# 10_ToMeasOutUI.net
KiCad netlist of a schematic drawn in Altium Designer
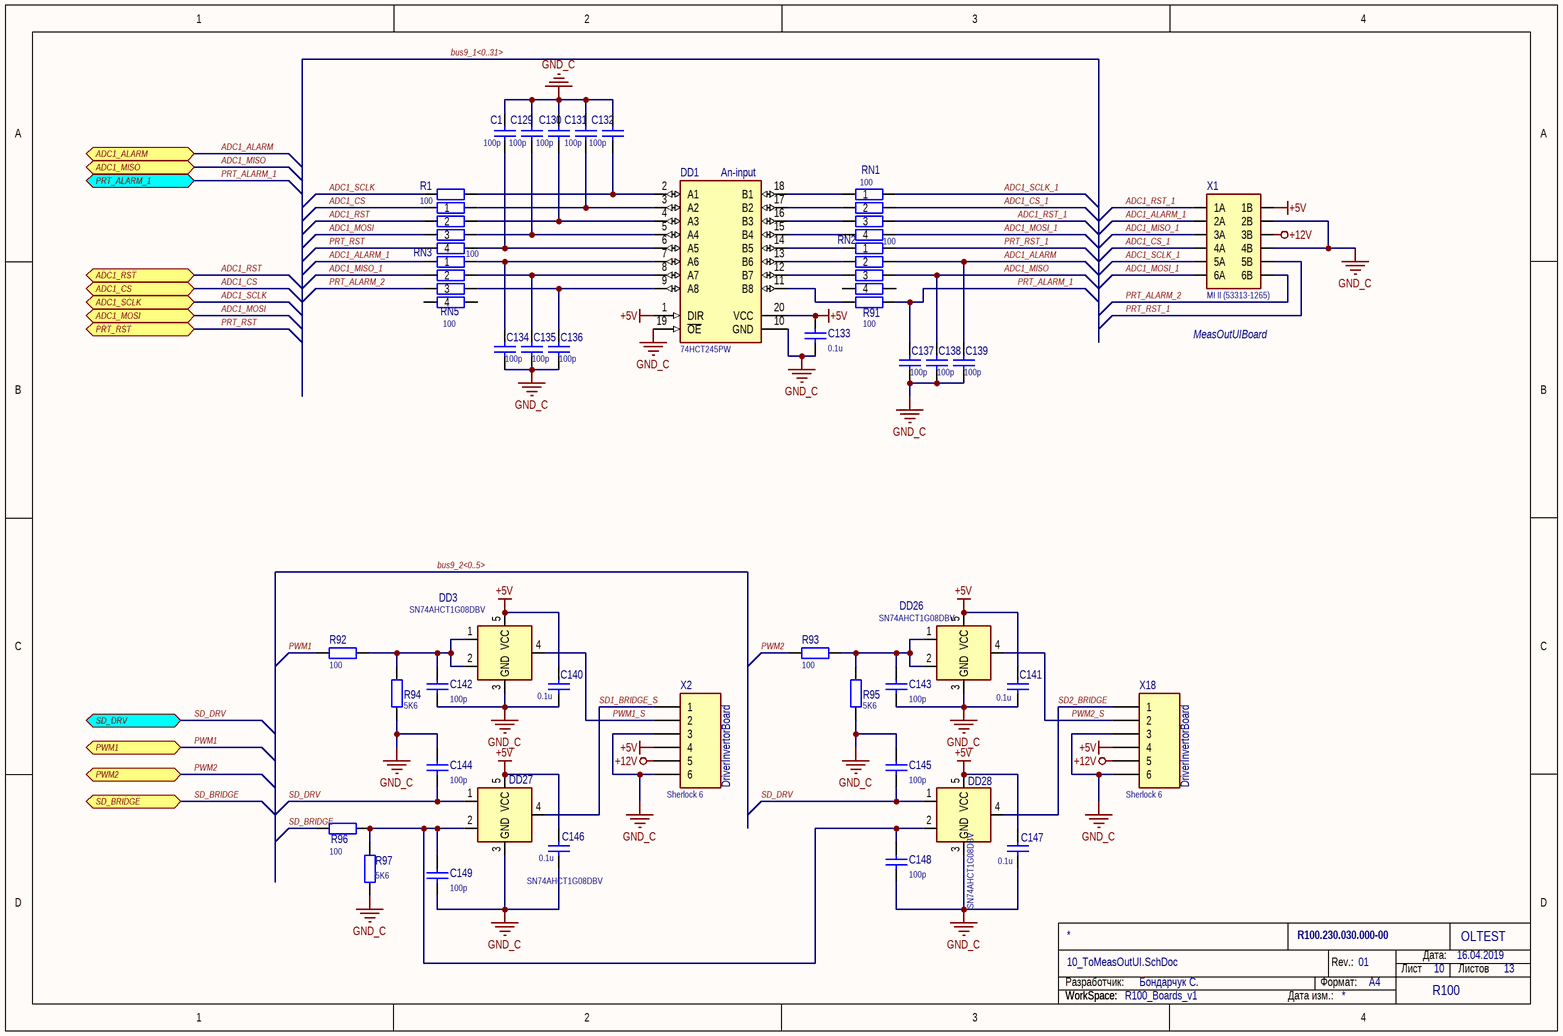
[diagram p0: 10_ToMeasOutUI.SchDoc]

(export (version "E")
  (design (tool "Eeschema 10.0.6"))
  (components
    (comp (ref "C1")
      (value "100p")
      (footprint "mainLib:SMD_C_0603")
      (description "SMD C 0603 MURATA 100V 5% NP0")
      (fields (field (name "PARTNUMBER") "GRM1885C2A101JA01") (field (name "MANUFACTURER") "MURATA"))
      (libsource (lib "mainRCLib") (part "C0603 100p 100V 5%"))
    )
    (comp (ref "C129")
      (value "100p")
      (footprint "mainLib:SMD_C_0603")
      (description "SMD C 0603 MURATA 100V 5% NP0")
      (fields (field (name "PARTNUMBER") "GRM1885C2A101JA01") (field (name "MANUFACTURER") "MURATA"))
      (libsource (lib "mainRCLib") (part "C0603 100p 100V 5%"))
    )
    (comp (ref "C130")
      (value "100p")
      (footprint "mainLib:SMD_C_0603")
      (description "SMD C 0603 MURATA 100V 5% NP0")
      (fields (field (name "PARTNUMBER") "GRM1885C2A101JA01") (field (name "MANUFACTURER") "MURATA"))
      (libsource (lib "mainRCLib") (part "C0603 100p 100V 5%"))
    )
    (comp (ref "C131")
      (value "100p")
      (footprint "mainLib:SMD_C_0603")
      (description "SMD C 0603 MURATA 100V 5% NP0")
      (fields (field (name "PARTNUMBER") "GRM1885C2A101JA01") (field (name "MANUFACTURER") "MURATA"))
      (libsource (lib "mainRCLib") (part "C0603 100p 100V 5%"))
    )
    (comp (ref "C132")
      (value "100p")
      (footprint "mainLib:SMD_C_0603")
      (description "SMD C 0603 MURATA 100V 5% NP0")
      (fields (field (name "PARTNUMBER") "GRM1885C2A101JA01") (field (name "MANUFACTURER") "MURATA"))
      (libsource (lib "mainRCLib") (part "C0603 100p 100V 5%"))
    )
    (comp (ref "C133")
      (value "0.1u")
      (footprint "mainLib:SMD_C_0603")
      (description "SMD C 0603 MURATA 50V 10% X7R")
      (fields (field (name "PARTNUMBER") "GRM188R71H104K") (field (name "MANUFACTURER") "MURATA"))
      (libsource (lib "mainRCLib") (part "C0603 0.1u 50V 10%"))
    )
    (comp (ref "C134")
      (value "100p")
      (footprint "mainLib:SMD_C_0603")
      (description "SMD C 0603 MURATA 100V 5% NP0")
      (fields (field (name "PARTNUMBER") "GRM1885C2A101JA01") (field (name "MANUFACTURER") "MURATA"))
      (libsource (lib "mainRCLib") (part "C0603 100p 100V 5%"))
    )
    (comp (ref "C135")
      (value "100p")
      (footprint "mainLib:SMD_C_0603")
      (description "SMD C 0603 MURATA 100V 5% NP0")
      (fields (field (name "PARTNUMBER") "GRM1885C2A101JA01") (field (name "MANUFACTURER") "MURATA"))
      (libsource (lib "mainRCLib") (part "C0603 100p 100V 5%"))
    )
    (comp (ref "C136")
      (value "100p")
      (footprint "mainLib:SMD_C_0603")
      (description "SMD C 0603 MURATA 100V 5% NP0")
      (fields (field (name "PARTNUMBER") "GRM1885C2A101JA01") (field (name "MANUFACTURER") "MURATA"))
      (libsource (lib "mainRCLib") (part "C0603 100p 100V 5%"))
    )
    (comp (ref "C137")
      (value "100p")
      (footprint "mainLib:SMD_C_0603")
      (description "SMD C 0603 MURATA 100V 5% NP0")
      (fields (field (name "PARTNUMBER") "GRM1885C2A101JA01") (field (name "MANUFACTURER") "MURATA"))
      (libsource (lib "mainRCLib") (part "C0603 100p 100V 5%"))
    )
    (comp (ref "C138")
      (value "100p")
      (footprint "mainLib:SMD_C_0603")
      (description "SMD C 0603 MURATA 100V 5% NP0")
      (fields (field (name "PARTNUMBER") "GRM1885C2A101JA01") (field (name "MANUFACTURER") "MURATA"))
      (libsource (lib "mainRCLib") (part "C0603 100p 100V 5%"))
    )
    (comp (ref "C139")
      (value "100p")
      (footprint "mainLib:SMD_C_0603")
      (description "SMD C 0603 MURATA 100V 5% NP0")
      (fields (field (name "PARTNUMBER") "GRM1885C2A101JA01") (field (name "MANUFACTURER") "MURATA"))
      (libsource (lib "mainRCLib") (part "C0603 100p 100V 5%"))
    )
    (comp (ref "C140")
      (value "0.1u")
      (footprint "mainLib:SMD_C_0603")
      (description "SMD C 0603 MURATA 50V 10% X7R")
      (fields (field (name "PARTNUMBER") "GRM188R71H104K") (field (name "MANUFACTURER") "MURATA"))
      (libsource (lib "mainRCLib") (part "C0603 0.1u 50V 10%"))
    )
    (comp (ref "C141")
      (value "0.1u")
      (footprint "mainLib:SMD_C_0603")
      (description "SMD C 0603 MURATA 50V 10% X7R")
      (fields (field (name "PARTNUMBER") "GRM188R71H104K") (field (name "MANUFACTURER") "MURATA"))
      (libsource (lib "mainRCLib") (part "C0603 0.1u 50V 10%"))
    )
    (comp (ref "C142")
      (value "100p")
      (footprint "mainLib:SMD_C_0603")
      (description "SMD C 0603 MURATA 100V 5% NP0")
      (fields (field (name "PARTNUMBER") "GRM1885C2A101JA01") (field (name "MANUFACTURER") "MURATA"))
      (libsource (lib "mainRCLib") (part "C0603 100p 100V 5%"))
    )
    (comp (ref "C143")
      (value "100p")
      (footprint "mainLib:SMD_C_0603")
      (description "SMD C 0603 MURATA 100V 5% NP0")
      (fields (field (name "PARTNUMBER") "GRM1885C2A101JA01") (field (name "MANUFACTURER") "MURATA"))
      (libsource (lib "mainRCLib") (part "C0603 100p 100V 5%"))
    )
    (comp (ref "C144")
      (value "100p")
      (footprint "mainLib:SMD_C_0603")
      (description "SMD C 0603 MURATA 100V 5% NP0")
      (fields (field (name "PARTNUMBER") "GRM1885C2A101JA01") (field (name "MANUFACTURER") "MURATA"))
      (libsource (lib "mainRCLib") (part "C0603 100p 100V 5%"))
    )
    (comp (ref "C145")
      (value "100p")
      (footprint "mainLib:SMD_C_0603")
      (description "SMD C 0603 MURATA 100V 5% NP0")
      (fields (field (name "PARTNUMBER") "GRM1885C2A101JA01") (field (name "MANUFACTURER") "MURATA"))
      (libsource (lib "mainRCLib") (part "C0603 100p 100V 5%"))
    )
    (comp (ref "C146")
      (value "0.1u")
      (footprint "mainLib:SMD_C_0603")
      (description "SMD C 0603 MURATA 50V 10% X7R")
      (fields (field (name "PARTNUMBER") "GRM188R71H104K") (field (name "MANUFACTURER") "MURATA"))
      (libsource (lib "mainRCLib") (part "C0603 0.1u 50V 10%"))
    )
    (comp (ref "C147")
      (value "0.1u")
      (footprint "mainLib:SMD_C_0603")
      (description "SMD C 0603 MURATA 50V 10% X7R")
      (fields (field (name "PARTNUMBER") "GRM188R71H104K") (field (name "MANUFACTURER") "MURATA"))
      (libsource (lib "mainRCLib") (part "C0603 0.1u 50V 10%"))
    )
    (comp (ref "C148")
      (value "100p")
      (footprint "mainLib:SMD_C_0603")
      (description "SMD C 0603 MURATA 100V 5% NP0")
      (fields (field (name "PARTNUMBER") "GRM1885C2A101JA01") (field (name "MANUFACTURER") "MURATA"))
      (libsource (lib "mainRCLib") (part "C0603 100p 100V 5%"))
    )
    (comp (ref "C149")
      (value "100p")
      (footprint "mainLib:SMD_C_0603")
      (description "SMD C 0603 MURATA 100V 5% NP0")
      (fields (field (name "PARTNUMBER") "GRM1885C2A101JA01") (field (name "MANUFACTURER") "MURATA"))
      (libsource (lib "mainRCLib") (part "C0603 100p 100V 5%"))
    )
    (comp (ref "DD1")
      (value "74HCT245PW")
      (footprint "mainLib:PW0020A_M")
      (description "Octal Bus Transceivers With 3-State Outputs, PW0020A")
      (fields (field (name "MANUFACTURER") "NXP"))
      (libsource (lib "mainLib") (part "74HCT245PW"))
    )
    (comp (ref "DD3")
      (value "SN74AHCT1G08DBV")
      (footprint "mainLib:SOT-23(DBV)")
      (description "2-in AND")
      (fields (field (name "MANUFACTURER") "Texas Instruments"))
      (libsource (lib "mainLib") (part "SN74AHCT1G08DBV"))
    )
    (comp (ref "DD26")
      (value "SN74AHCT1G08DBV")
      (footprint "mainLib:SOT-23(DBV)")
      (description "2-in AND")
      (fields (field (name "MANUFACTURER") "Texas Instruments"))
      (libsource (lib "mainLib") (part "SN74AHCT1G08DBV"))
    )
    (comp (ref "DD27")
      (value "SN74AHCT1G08DBV")
      (footprint "mainLib:SOT-23(DBV)")
      (description "2-in AND")
      (fields (field (name "MANUFACTURER") "Texas Instruments"))
      (libsource (lib "mainLib") (part "SN74AHCT1G08DBV"))
    )
    (comp (ref "DD28")
      (value "SN74AHCT1G08DBV")
      (footprint "mainLib:SOT-23(DBV)")
      (description "2-in AND")
      (fields (field (name "MANUFACTURER") "Texas Instruments"))
      (libsource (lib "mainLib") (part "SN74AHCT1G08DBV"))
    )
    (comp (ref "R1")
      (value "100")
      (footprint "SMD_R_0603")
      (description "SMD R 0603 VISHAY 0.1W 75V 1% 100ppm")
      (fields (field (name "PARTNUMBER") "CRCW0603100RFK") (field (name "MANUFACTURER") "VISHAY"))
      (libsource (lib "mainRCLib") (part "R0603 100 1%"))
    )
    (comp (ref "R91")
      (value "100")
      (footprint "SMD_R_0603")
      (description "SMD R 0603 VISHAY 0.1W 75V 1% 100ppm")
      (fields (field (name "PARTNUMBER") "CRCW0603100RFK") (field (name "MANUFACTURER") "VISHAY"))
      (libsource (lib "mainRCLib") (part "R0603 100 1%"))
    )
    (comp (ref "R92")
      (value "100")
      (footprint "SMD_R_0603")
      (description "SMD R 0603 VISHAY 0.1W 75V 1% 100ppm")
      (fields (field (name "PARTNUMBER") "CRCW0603100RFK") (field (name "MANUFACTURER") "VISHAY"))
      (libsource (lib "mainRCLib") (part "R0603 100 1%"))
    )
    (comp (ref "R93")
      (value "100")
      (footprint "SMD_R_0603")
      (description "SMD R 0603 VISHAY 0.1W 75V 1% 100ppm")
      (fields (field (name "PARTNUMBER") "CRCW0603100RFK") (field (name "MANUFACTURER") "VISHAY"))
      (libsource (lib "mainRCLib") (part "R0603 100 1%"))
    )
    (comp (ref "R94")
      (value "5K6")
      (footprint "mainLib:SMD_R_0603")
      (description "SMD R 0603 VISHAY 0.1W 75V 1% 100ppm")
      (fields (field (name "PARTNUMBER") "CRCW06035K60FK") (field (name "MANUFACTURER") "VISHAY"))
      (libsource (lib "mainRCLib") (part "R0603 5K6 1%"))
    )
    (comp (ref "R95")
      (value "5K6")
      (footprint "mainLib:SMD_R_0603")
      (description "SMD R 0603 VISHAY 0.1W 75V 1% 100ppm")
      (fields (field (name "PARTNUMBER") "CRCW06035K60FK") (field (name "MANUFACTURER") "VISHAY"))
      (libsource (lib "mainRCLib") (part "R0603 5K6 1%"))
    )
    (comp (ref "R96")
      (value "100")
      (footprint "SMD_R_0603")
      (description "SMD R 0603 VISHAY 0.1W 75V 1% 100ppm")
      (fields (field (name "PARTNUMBER") "CRCW0603100RFK") (field (name "MANUFACTURER") "VISHAY"))
      (libsource (lib "mainRCLib") (part "R0603 100 1%"))
    )
    (comp (ref "R97")
      (value "5K6")
      (footprint "mainLib:SMD_R_0603")
      (description "SMD R 0603 VISHAY 0.1W 75V 1% 100ppm")
      (fields (field (name "PARTNUMBER") "CRCW06035K60FK") (field (name "MANUFACTURER") "VISHAY"))
      (libsource (lib "mainRCLib") (part "R0603 5K6 1%"))
    )
    (comp (ref "RN1")
      (value "100")
      (footprint "mainLib:CRA06S")
      (description "SMD RESISTOR ARRAY VISHAY 0.063W 50V 1% 100ppm")
      (fields (field (name "PARTNUMBER") "CRA06S083100RF") (field (name "MANUFACTURER") "VISHAY"))
      (libsource (lib "mainRCLib") (part "CRA06S 4x100 1%"))
    )
    (comp (ref "RN2")
      (value "100")
      (footprint "mainLib:CRA06S")
      (description "SMD RESISTOR ARRAY VISHAY 0.063W 50V 1% 100ppm")
      (fields (field (name "PARTNUMBER") "CRA06S083100RF") (field (name "MANUFACTURER") "VISHAY"))
      (libsource (lib "mainRCLib") (part "CRA06S 4x100 1%"))
    )
    (comp (ref "RN3")
      (value "100")
      (footprint "mainLib:CRA06S")
      (description "SMD RESISTOR ARRAY VISHAY 0.063W 50V 1% 100ppm")
      (fields (field (name "PARTNUMBER") "CRA06S083100RF") (field (name "MANUFACTURER") "VISHAY"))
      (libsource (lib "mainRCLib") (part "CRA06S 4x100 1%"))
    )
    (comp (ref "RN5")
      (value "100")
      (footprint "mainLib:CRA06S")
      (description "SMD RESISTOR ARRAY VISHAY 0.063W 50V 1% 100ppm")
      (fields (field (name "PARTNUMBER") "CRA06S083100RF") (field (name "MANUFACTURER") "VISHAY"))
      (libsource (lib "mainRCLib") (part "CRA06S 4x100 1%"))
    )
    (comp (ref "X1")
      (value "MI II (53313-1265)")
      (footprint "mainLib:53313-1265")
      (description "MI II 12 (6x2row), 2A 125V 2mm")
      (fields (field (name "PARTNUMBER") "53313-1265") (field (name "MANUFACTURER") "MOLEX"))
      (libsource (lib "mainLib") (part "53313-1265"))
    )
    (comp (ref "X2")
      (value "Sherlock 6")
      (footprint "mainLib:35362-0650")
      (description "Sherlock 6 Side, 2A 125V 2mm")
      (fields (field (name "PARTNUMBER") "35362-0650") (field (name "MANUFACTURER") "MOLEX"))
      (libsource (lib "mainLib") (part "35363-0650"))
    )
    (comp (ref "X18")
      (value "Sherlock 6")
      (footprint "mainLib:35362-0650")
      (description "Sherlock 6 Side, 2A 125V 2mm")
      (fields (field (name "PARTNUMBER") "35362-0650") (field (name "MANUFACTURER") "MOLEX"))
      (libsource (lib "mainLib") (part "35363-0650"))
    )
  )
  (nets
    (net (code "3") (name "+5V") (class "Default")
      (node (ref "C133") (pin "2") (pinfunction "2_2") (pintype "passive"))
      (node (ref "C140") (pin "2") (pinfunction "2_2") (pintype "passive"))
      (node (ref "C141") (pin "2") (pinfunction "2_2") (pintype "passive"))
      (node (ref "C146") (pin "2") (pinfunction "2_2") (pintype "passive"))
      (node (ref "C147") (pin "2") (pinfunction "2_2") (pintype "passive"))
      (node (ref "DD1") (pin "1") (pinfunction "DIR_1") (pintype "input"))
      (node (ref "DD1") (pin "20") (pinfunction "VCC_20") (pintype "power_in"))
      (node (ref "DD26") (pin "5") (pinfunction "VCC_5") (pintype "passive"))
      (node (ref "DD27") (pin "5") (pinfunction "VCC_5") (pintype "passive"))
      (node (ref "DD28") (pin "5") (pinfunction "VCC_5") (pintype "passive"))
      (node (ref "DD3") (pin "5") (pinfunction "VCC_5") (pintype "passive"))
      (node (ref "X1") (pin "1B") (pinfunction "1B_1B") (pintype "passive"))
      (node (ref "X18") (pin "4") (pinfunction "4_4") (pintype "passive"))
      (node (ref "X2") (pin "4") (pinfunction "4_4") (pintype "passive"))
    )
    (net (code "4") (name "+12V") (class "Default")
      (node (ref "X1") (pin "3B") (pinfunction "3B_3B") (pintype "passive"))
      (node (ref "X18") (pin "5") (pinfunction "5_5") (pintype "passive"))
      (node (ref "X2") (pin "5") (pinfunction "5_5") (pintype "passive"))
    )
    (net (code "5") (name "/ADC1_ALARM") (class "Default")
      (node (ref "C139") (pin "2") (pinfunction "2_2") (pintype "passive"))
      (node (ref "RN2") (pin "7") (pinfunction "7_7") (pintype "passive"))
    )
    (net (code "6") (name "/ADC1_ALARM_1") (class "Default")
      (node (ref "RN5") (pin "1") (pinfunction "1_1") (pintype "passive"))
      (node (ref "X1") (pin "2A") (pinfunction "2A_2A") (pintype "passive"))
    )
    (net (code "7") (name "/ADC1_CS") (class "Default")
      (node (ref "RN3") (pin "1") (pinfunction "1_1") (pintype "passive"))
    )
    (net (code "8") (name "/ADC1_CS_1") (class "Default")
      (node (ref "RN1") (pin "7") (pinfunction "7_7") (pintype "passive"))
      (node (ref "X1") (pin "4A") (pinfunction "4A_4A") (pintype "passive"))
    )
    (net (code "9") (name "/ADC1_MISO") (class "Default")
      (node (ref "C138") (pin "2") (pinfunction "2_2") (pintype "passive"))
      (node (ref "RN2") (pin "6") (pinfunction "6_6") (pintype "passive"))
    )
    (net (code "10") (name "/ADC1_MISO_1") (class "Default")
      (node (ref "RN5") (pin "2") (pinfunction "2_2") (pintype "passive"))
      (node (ref "X1") (pin "3A") (pinfunction "3A_3A") (pintype "passive"))
    )
    (net (code "11") (name "/ADC1_MOSI") (class "Default")
      (node (ref "RN3") (pin "3") (pinfunction "3_3") (pintype "passive"))
    )
    (net (code "12") (name "/ADC1_MOSI_1") (class "Default")
      (node (ref "RN1") (pin "5") (pinfunction "5_5") (pintype "passive"))
      (node (ref "X1") (pin "6A") (pinfunction "6A_6A") (pintype "passive"))
    )
    (net (code "13") (name "/ADC1_RST") (class "Default")
      (node (ref "RN3") (pin "2") (pinfunction "2_2") (pintype "passive"))
    )
    (net (code "14") (name "/ADC1_RST_1") (class "Default")
      (node (ref "RN1") (pin "6") (pinfunction "6_6") (pintype "passive"))
      (node (ref "X1") (pin "1A") (pinfunction "1A_1A") (pintype "passive"))
    )
    (net (code "15") (name "/ADC1_SCLK") (class "Default")
      (node (ref "R1") (pin "1") (pinfunction "1_1") (pintype "passive"))
    )
    (net (code "16") (name "/ADC1_SCLK_1") (class "Default")
      (node (ref "RN1") (pin "8") (pinfunction "8_8") (pintype "passive"))
      (node (ref "X1") (pin "5A") (pinfunction "5A_5A") (pintype "passive"))
    )
    (net (code "17") (name "/PRT_ALARM_1") (class "Default")
      (node (ref "C137") (pin "2") (pinfunction "2_2") (pintype "passive"))
      (node (ref "R91") (pin "2") (pinfunction "2_2") (pintype "passive"))
    )
    (net (code "18") (name "/PRT_ALARM_2") (class "Default")
      (node (ref "RN5") (pin "3") (pinfunction "3_3") (pintype "passive"))
      (node (ref "X1") (pin "6B") (pinfunction "6B_6B") (pintype "passive"))
    )
    (net (code "19") (name "/PRT_RST") (class "Default")
      (node (ref "RN3") (pin "4") (pinfunction "4_4") (pintype "passive"))
    )
    (net (code "20") (name "/PRT_RST_1") (class "Default")
      (node (ref "RN2") (pin "8") (pinfunction "8_8") (pintype "passive"))
      (node (ref "X1") (pin "5B") (pinfunction "5B_5B") (pintype "passive"))
    )
    (net (code "21") (name "/PWM1") (class "Default")
      (node (ref "R92") (pin "1") (pinfunction "1_1") (pintype "passive"))
    )
    (net (code "22") (name "/PWM1_S") (class "Default")
      (node (ref "DD3") (pin "4") (pintype "passive"))
      (node (ref "X2") (pin "2") (pinfunction "2_2") (pintype "passive"))
    )
    (net (code "23") (name "/PWM2") (class "Default")
      (node (ref "R93") (pin "1") (pinfunction "1_1") (pintype "passive"))
    )
    (net (code "24") (name "/PWM2_S") (class "Default")
      (node (ref "DD26") (pin "4") (pintype "passive"))
      (node (ref "X18") (pin "2") (pinfunction "2_2") (pintype "passive"))
    )
    (net (code "25") (name "/SD1_BRIDGE_S") (class "Default")
      (node (ref "DD27") (pin "4") (pintype "passive"))
      (node (ref "X2") (pin "1") (pinfunction "1_1") (pintype "passive"))
    )
    (net (code "26") (name "/SD2_BRIDGE") (class "Default")
      (node (ref "DD28") (pin "4") (pintype "passive"))
      (node (ref "X18") (pin "1") (pinfunction "1_1") (pintype "passive"))
    )
    (net (code "27") (name "/SD_BRIDGE") (class "Default")
      (node (ref "R96") (pin "1") (pinfunction "1_1") (pintype "passive"))
    )
    (net (code "28") (name "/SD_DRV") (class "Default")
      (node (ref "C144") (pin "1") (pinfunction "1_1") (pintype "passive"))
      (node (ref "C145") (pin "1") (pinfunction "1_1") (pintype "passive"))
      (node (ref "DD27") (pin "1") (pintype "passive"))
      (node (ref "DD28") (pin "1") (pintype "passive"))
    )
    (net (code "31") (name "GND_C") (class "Default")
      (node (ref "C1") (pin "1") (pinfunction "1_1") (pintype "passive"))
      (node (ref "C129") (pin "1") (pinfunction "1_1") (pintype "passive"))
      (node (ref "C130") (pin "1") (pinfunction "1_1") (pintype "passive"))
      (node (ref "C131") (pin "1") (pinfunction "1_1") (pintype "passive"))
      (node (ref "C132") (pin "1") (pinfunction "1_1") (pintype "passive"))
      (node (ref "C133") (pin "1") (pinfunction "1_1") (pintype "passive"))
      (node (ref "C134") (pin "1") (pinfunction "1_1") (pintype "passive"))
      (node (ref "C135") (pin "1") (pinfunction "1_1") (pintype "passive"))
      (node (ref "C136") (pin "1") (pinfunction "1_1") (pintype "passive"))
      (node (ref "C137") (pin "1") (pinfunction "1_1") (pintype "passive"))
      (node (ref "C138") (pin "1") (pinfunction "1_1") (pintype "passive"))
      (node (ref "C139") (pin "1") (pinfunction "1_1") (pintype "passive"))
      (node (ref "C140") (pin "1") (pinfunction "1_1") (pintype "passive"))
      (node (ref "C141") (pin "1") (pinfunction "1_1") (pintype "passive"))
      (node (ref "C142") (pin "1") (pinfunction "1_1") (pintype "passive"))
      (node (ref "C143") (pin "1") (pinfunction "1_1") (pintype "passive"))
      (node (ref "C144") (pin "2") (pinfunction "2_2") (pintype "passive"))
      (node (ref "C145") (pin "2") (pinfunction "2_2") (pintype "passive"))
      (node (ref "C146") (pin "1") (pinfunction "1_1") (pintype "passive"))
      (node (ref "C147") (pin "1") (pinfunction "1_1") (pintype "passive"))
      (node (ref "C148") (pin "1") (pinfunction "1_1") (pintype "passive"))
      (node (ref "C149") (pin "1") (pinfunction "1_1") (pintype "passive"))
      (node (ref "DD1") (pin "10") (pinfunction "GND_10") (pintype "power_in"))
      (node (ref "DD1") (pin "19") (pinfunction "~{OE}_19") (pintype "input"))
      (node (ref "DD26") (pin "3") (pinfunction "GND_3") (pintype "passive"))
      (node (ref "DD27") (pin "3") (pinfunction "GND_3") (pintype "passive"))
      (node (ref "DD28") (pin "3") (pinfunction "GND_3") (pintype "passive"))
      (node (ref "DD3") (pin "3") (pinfunction "GND_3") (pintype "passive"))
      (node (ref "R94") (pin "1") (pinfunction "1_1") (pintype "passive"))
      (node (ref "R95") (pin "1") (pinfunction "1_1") (pintype "passive"))
      (node (ref "R97") (pin "1") (pinfunction "1_1") (pintype "passive"))
      (node (ref "X1") (pin "2B") (pinfunction "2B_2B") (pintype "passive"))
      (node (ref "X1") (pin "4B") (pinfunction "4B_4B") (pintype "passive"))
      (node (ref "X18") (pin "3") (pinfunction "3_3") (pintype "passive"))
      (node (ref "X18") (pin "6") (pinfunction "6_6") (pintype "passive"))
      (node (ref "X2") (pin "3") (pinfunction "3_3") (pintype "passive"))
      (node (ref "X2") (pin "6") (pinfunction "6_6") (pintype "passive"))
    )
    (net (code "32") (name "Net-(C142-Pad2)") (class "Default")
      (node (ref "C142") (pin "2") (pinfunction "2_2") (pintype "passive"))
      (node (ref "DD3") (pin "1") (pintype "passive"))
      (node (ref "DD3") (pin "2") (pintype "passive"))
      (node (ref "R92") (pin "2") (pinfunction "2_2") (pintype "passive"))
      (node (ref "R94") (pin "2") (pinfunction "2_2") (pintype "passive"))
    )
    (net (code "33") (name "Net-(C143-Pad2)") (class "Default")
      (node (ref "C143") (pin "2") (pinfunction "2_2") (pintype "passive"))
      (node (ref "DD26") (pin "1") (pintype "passive"))
      (node (ref "DD26") (pin "2") (pintype "passive"))
      (node (ref "R93") (pin "2") (pinfunction "2_2") (pintype "passive"))
      (node (ref "R95") (pin "2") (pinfunction "2_2") (pintype "passive"))
    )
    (net (code "34") (name "Net-(C148-Pad2)") (class "Default")
      (node (ref "C148") (pin "2") (pinfunction "2_2") (pintype "passive"))
      (node (ref "C149") (pin "2") (pinfunction "2_2") (pintype "passive"))
      (node (ref "DD27") (pin "2") (pintype "passive"))
      (node (ref "DD28") (pin "2") (pintype "passive"))
      (node (ref "R96") (pin "2") (pinfunction "2_2") (pintype "passive"))
      (node (ref "R97") (pin "2") (pinfunction "2_2") (pintype "passive"))
    )
    (net (code "35") (name "Net-(DD1-A1)") (class "Default")
      (node (ref "C132") (pin "2") (pinfunction "2_2") (pintype "passive"))
      (node (ref "DD1") (pin "2") (pinfunction "A1_2") (pintype "bidirectional"))
      (node (ref "R1") (pin "2") (pinfunction "2_2") (pintype "passive"))
    )
    (net (code "36") (name "Net-(DD1-A2)") (class "Default")
      (node (ref "C131") (pin "2") (pinfunction "2_2") (pintype "passive"))
      (node (ref "DD1") (pin "3") (pinfunction "A2_3") (pintype "bidirectional"))
      (node (ref "RN3") (pin "8") (pinfunction "8_8") (pintype "passive"))
    )
    (net (code "37") (name "Net-(DD1-A3)") (class "Default")
      (node (ref "C130") (pin "2") (pinfunction "2_2") (pintype "passive"))
      (node (ref "DD1") (pin "4") (pinfunction "A3_4") (pintype "bidirectional"))
      (node (ref "RN3") (pin "7") (pinfunction "7_7") (pintype "passive"))
    )
    (net (code "38") (name "Net-(DD1-A4)") (class "Default")
      (node (ref "C129") (pin "2") (pinfunction "2_2") (pintype "passive"))
      (node (ref "DD1") (pin "5") (pinfunction "A4_5") (pintype "bidirectional"))
      (node (ref "RN3") (pin "6") (pinfunction "6_6") (pintype "passive"))
    )
    (net (code "39") (name "Net-(DD1-A5)") (class "Default")
      (node (ref "C1") (pin "2") (pinfunction "2_2") (pintype "passive"))
      (node (ref "DD1") (pin "6") (pinfunction "A5_6") (pintype "bidirectional"))
      (node (ref "RN3") (pin "5") (pinfunction "5_5") (pintype "passive"))
    )
    (net (code "40") (name "Net-(DD1-A6)") (class "Default")
      (node (ref "C134") (pin "2") (pinfunction "2_2") (pintype "passive"))
      (node (ref "DD1") (pin "7") (pinfunction "A6_7") (pintype "bidirectional"))
      (node (ref "RN5") (pin "8") (pinfunction "8_8") (pintype "passive"))
    )
    (net (code "41") (name "Net-(DD1-A7)") (class "Default")
      (node (ref "C135") (pin "2") (pinfunction "2_2") (pintype "passive"))
      (node (ref "DD1") (pin "8") (pinfunction "A7_8") (pintype "bidirectional"))
      (node (ref "RN5") (pin "7") (pinfunction "7_7") (pintype "passive"))
    )
    (net (code "42") (name "Net-(DD1-A8)") (class "Default")
      (node (ref "C136") (pin "2") (pinfunction "2_2") (pintype "passive"))
      (node (ref "DD1") (pin "9") (pinfunction "A8_9") (pintype "bidirectional"))
      (node (ref "RN5") (pin "6") (pinfunction "6_6") (pintype "passive"))
    )
    (net (code "43") (name "Net-(DD1-B1)") (class "Default")
      (node (ref "DD1") (pin "18") (pinfunction "B1_18") (pintype "bidirectional"))
      (node (ref "RN1") (pin "1") (pinfunction "1_1") (pintype "passive"))
    )
    (net (code "44") (name "Net-(DD1-B2)") (class "Default")
      (node (ref "DD1") (pin "17") (pinfunction "B2_17") (pintype "bidirectional"))
      (node (ref "RN1") (pin "2") (pinfunction "2_2") (pintype "passive"))
    )
    (net (code "45") (name "Net-(DD1-B3)") (class "Default")
      (node (ref "DD1") (pin "16") (pinfunction "B3_16") (pintype "bidirectional"))
      (node (ref "RN1") (pin "3") (pinfunction "3_3") (pintype "passive"))
    )
    (net (code "46") (name "Net-(DD1-B4)") (class "Default")
      (node (ref "DD1") (pin "15") (pinfunction "B4_15") (pintype "bidirectional"))
      (node (ref "RN1") (pin "4") (pinfunction "4_4") (pintype "passive"))
    )
    (net (code "47") (name "Net-(DD1-B5)") (class "Default")
      (node (ref "DD1") (pin "14") (pinfunction "B5_14") (pintype "bidirectional"))
      (node (ref "RN2") (pin "1") (pinfunction "1_1") (pintype "passive"))
    )
    (net (code "48") (name "Net-(DD1-B6)") (class "Default")
      (node (ref "DD1") (pin "13") (pinfunction "B6_13") (pintype "bidirectional"))
      (node (ref "RN2") (pin "2") (pinfunction "2_2") (pintype "passive"))
    )
    (net (code "49") (name "Net-(DD1-B7)") (class "Default")
      (node (ref "DD1") (pin "12") (pinfunction "B7_12") (pintype "bidirectional"))
      (node (ref "RN2") (pin "3") (pinfunction "3_3") (pintype "passive"))
    )
    (net (code "50") (name "Net-(DD1-B8)") (class "Default")
      (node (ref "DD1") (pin "11") (pinfunction "B8_11") (pintype "bidirectional"))
      (node (ref "R91") (pin "1") (pinfunction "1_1") (pintype "passive"))
    )
    (net (code "51") (name "unconnected-(RN2-Pad4)") (class "Default")
      (node (ref "RN2") (pin "4") (pinfunction "4_4") (pintype "passive"))
    )
    (net (code "52") (name "unconnected-(RN2-Pad5)") (class "Default")
      (node (ref "RN2") (pin "5") (pinfunction "5_5") (pintype "passive"))
    )
    (net (code "53") (name "unconnected-(RN5-Pad4)") (class "Default")
      (node (ref "RN5") (pin "4") (pinfunction "4_4") (pintype "passive"))
    )
    (net (code "54") (name "unconnected-(RN5-Pad5)") (class "Default")
      (node (ref "RN5") (pin "5") (pinfunction "5_5") (pintype "passive"))
    )
  )
)
